# scem.net
KiCad netlist of a schematic drawn in EAGLE
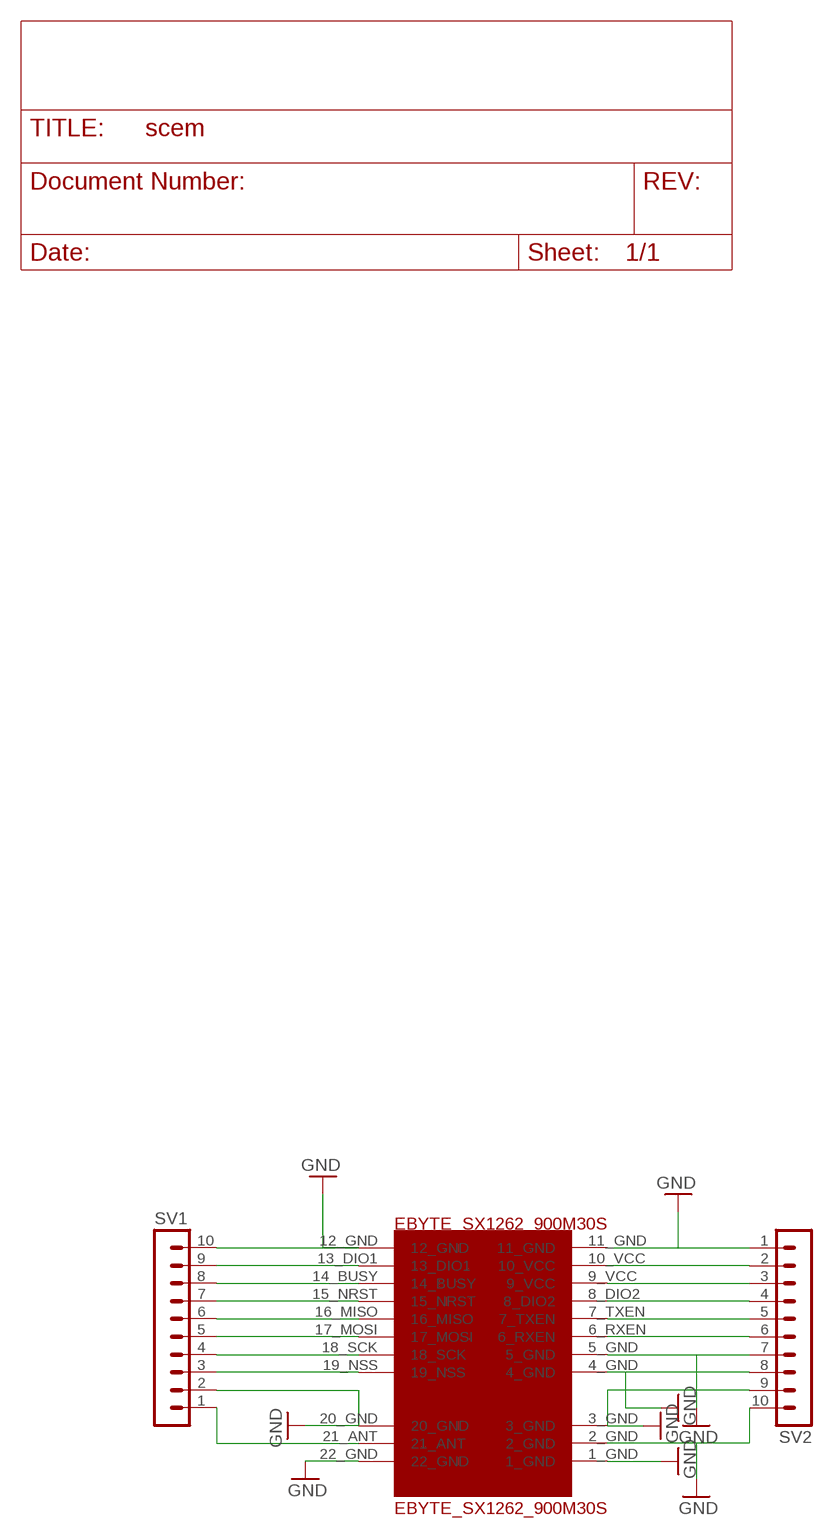
[diagram p0: schematic, sheet 1]

(export (version "E")
  (design (tool "Eeschema 10.0.6"))
  (components
    (comp (ref "EBYTE_SX1262_900M30S")
      (value "EBYTE_SX1262_900M30S")
      (footprint "eagle-import:EBYTE_SX1262_900M30S_FOOTPRINT")
      (libsource (lib "eagle-import") (part "EBYTE_SX1262_900M30S"))
    )
    (comp (ref "SV1")
      (value "MA10-1")
      (footprint "eagle-import:MA10-1")
      (libsource (lib "eagle-import") (part "MA10-1"))
    )
    (comp (ref "SV2")
      (value "MA10-1")
      (footprint "eagle-import:MA10-1")
      (libsource (lib "eagle-import") (part "MA10-1"))
    )
  )
  (nets
    (net (code "1") (name "GND") (class "Default")
      (node (ref "EBYTE_SX1262_900M30S") (pin "11_GND") (pinfunction "11_GND_11_GND") (pintype "power_in"))
      (node (ref "EBYTE_SX1262_900M30S") (pin "12_GND") (pinfunction "12_GND_12_GND") (pintype "power_in"))
      (node (ref "EBYTE_SX1262_900M30S") (pin "1_GND") (pinfunction "1_GND_1_GND") (pintype "power_in"))
      (node (ref "EBYTE_SX1262_900M30S") (pin "20_GND") (pinfunction "20_GND_20_GND") (pintype "power_in"))
      (node (ref "EBYTE_SX1262_900M30S") (pin "22_GND") (pinfunction "22_GND_22_GND") (pintype "power_in"))
      (node (ref "EBYTE_SX1262_900M30S") (pin "2_GND") (pinfunction "2_GND_2_GND") (pintype "power_in"))
      (node (ref "EBYTE_SX1262_900M30S") (pin "3_GND") (pinfunction "3_GND_3_GND") (pintype "power_in"))
      (node (ref "EBYTE_SX1262_900M30S") (pin "4_GND") (pinfunction "4_GND_4_GND") (pintype "power_in"))
      (node (ref "EBYTE_SX1262_900M30S") (pin "5_GND") (pinfunction "5_GND_5_GND") (pintype "power_in"))
      (node (ref "SV1") (pin "10") (pinfunction "10_10") (pintype "passive"))
      (node (ref "SV1") (pin "2") (pinfunction "2_2") (pintype "passive"))
      (node (ref "SV2") (pin "1") (pinfunction "1_1") (pintype "passive"))
      (node (ref "SV2") (pin "10") (pinfunction "10_10") (pintype "passive"))
      (node (ref "SV2") (pin "7") (pinfunction "7_7") (pintype "passive"))
      (node (ref "SV2") (pin "8") (pinfunction "8_8") (pintype "passive"))
      (node (ref "SV2") (pin "9") (pinfunction "9_9") (pintype "passive"))
    )
    (net (code "2") (name "Net-(EBYTE_SX1262_900M30S-Pad6_RXEN)") (class "Default")
      (node (ref "EBYTE_SX1262_900M30S") (pin "6_RXEN") (pinfunction "6_RXEN_6_RXEN") (pintype "bidirectional"))
      (node (ref "SV2") (pin "6") (pinfunction "6_6") (pintype "passive"))
    )
    (net (code "3") (name "Net-(EBYTE_SX1262_900M30S-Pad7_TXEN)") (class "Default")
      (node (ref "EBYTE_SX1262_900M30S") (pin "7_TXEN") (pinfunction "7_TXEN_7_TXEN") (pintype "bidirectional"))
      (node (ref "SV2") (pin "5") (pinfunction "5_5") (pintype "passive"))
    )
    (net (code "4") (name "Net-(EBYTE_SX1262_900M30S-Pad8_DIO2)") (class "Default")
      (node (ref "EBYTE_SX1262_900M30S") (pin "8_DIO2") (pinfunction "8_DIO2_8_DIO2") (pintype "bidirectional"))
      (node (ref "SV2") (pin "4") (pinfunction "4_4") (pintype "passive"))
    )
    (net (code "5") (name "Net-(EBYTE_SX1262_900M30S-Pad9_VCC)") (class "Default")
      (node (ref "EBYTE_SX1262_900M30S") (pin "9_VCC") (pinfunction "9_VCC_9_VCC") (pintype "power_in"))
      (node (ref "SV2") (pin "3") (pinfunction "3_3") (pintype "passive"))
    )
    (net (code "6") (name "Net-(EBYTE_SX1262_900M30S-Pad10_VCC)") (class "Default")
      (node (ref "EBYTE_SX1262_900M30S") (pin "10_VCC") (pinfunction "10_VCC_10_VCC") (pintype "power_in"))
      (node (ref "SV2") (pin "2") (pinfunction "2_2") (pintype "passive"))
    )
    (net (code "7") (name "Net-(EBYTE_SX1262_900M30S-Pad13_DIO1)") (class "Default")
      (node (ref "EBYTE_SX1262_900M30S") (pin "13_DIO1") (pinfunction "13_DIO1_13_DIO1") (pintype "bidirectional"))
      (node (ref "SV1") (pin "9") (pinfunction "9_9") (pintype "passive"))
    )
    (net (code "8") (name "Net-(EBYTE_SX1262_900M30S-Pad14_BUSY)") (class "Default")
      (node (ref "EBYTE_SX1262_900M30S") (pin "14_BUSY") (pinfunction "14_BUSY_14_BUSY") (pintype "bidirectional"))
      (node (ref "SV1") (pin "8") (pinfunction "8_8") (pintype "passive"))
    )
    (net (code "9") (name "Net-(EBYTE_SX1262_900M30S-Pad15_NRST)") (class "Default")
      (node (ref "EBYTE_SX1262_900M30S") (pin "15_NRST") (pinfunction "15_NRST_15_NRST") (pintype "bidirectional"))
      (node (ref "SV1") (pin "7") (pinfunction "7_7") (pintype "passive"))
    )
    (net (code "10") (name "Net-(EBYTE_SX1262_900M30S-Pad16_MISO)") (class "Default")
      (node (ref "EBYTE_SX1262_900M30S") (pin "16_MISO") (pinfunction "16_MISO_16_MISO") (pintype "bidirectional"))
      (node (ref "SV1") (pin "6") (pinfunction "6_6") (pintype "passive"))
    )
    (net (code "11") (name "Net-(EBYTE_SX1262_900M30S-Pad17_MOSI)") (class "Default")
      (node (ref "EBYTE_SX1262_900M30S") (pin "17_MOSI") (pinfunction "17_MOSI_17_MOSI") (pintype "bidirectional"))
      (node (ref "SV1") (pin "5") (pinfunction "5_5") (pintype "passive"))
    )
    (net (code "12") (name "Net-(EBYTE_SX1262_900M30S-Pad18_SCK)") (class "Default")
      (node (ref "EBYTE_SX1262_900M30S") (pin "18_SCK") (pinfunction "18_SCK_18_SCK") (pintype "bidirectional"))
      (node (ref "SV1") (pin "4") (pinfunction "4_4") (pintype "passive"))
    )
    (net (code "13") (name "Net-(EBYTE_SX1262_900M30S-Pad19_NSS)") (class "Default")
      (node (ref "EBYTE_SX1262_900M30S") (pin "19_NSS") (pinfunction "19_NSS_19_NSS") (pintype "bidirectional"))
      (node (ref "SV1") (pin "3") (pinfunction "3_3") (pintype "passive"))
    )
    (net (code "14") (name "Net-(EBYTE_SX1262_900M30S-Pad21_ANT)") (class "Default")
      (node (ref "EBYTE_SX1262_900M30S") (pin "21_ANT") (pinfunction "21_ANT_21_ANT") (pintype "bidirectional"))
      (node (ref "SV1") (pin "1") (pinfunction "1_1") (pintype "passive"))
    )
  )
)
